# Volga-PCB.net
KiCad netlist of a schematic drawn in Altium Designer
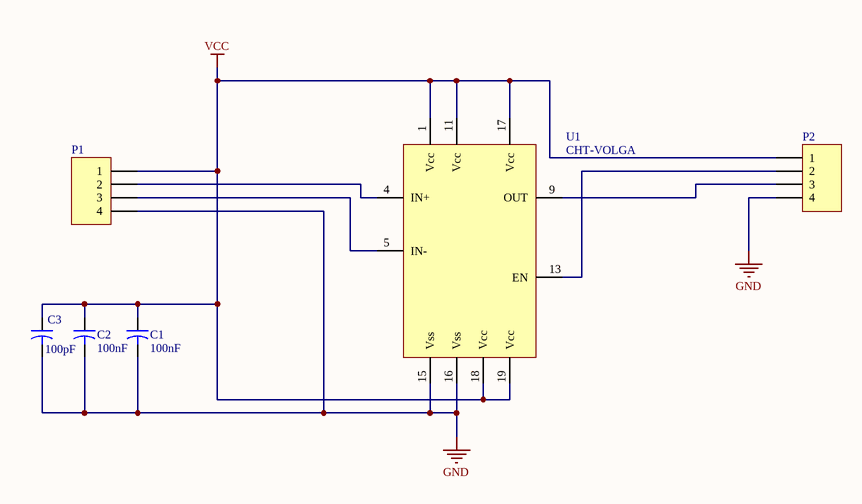
[diagram p0: Volga-PCB.SchDoc]

(export (version "E")
  (design (tool "Eeschema 10.0.6"))
  (components
    (comp (ref "C1")
      (value "100nF")
      (footprint "Dummy-10mm")
      (description "Capacitor-Dummy-THT")
      (fields (field (name "PUBLISHER") "Sebastian Kulik"))
      (libsource (lib "Capacitors") (part "Capacitor-Dummy-THT"))
    )
    (comp (ref "C2")
      (value "100nF")
      (footprint "Dummy-10mm")
      (description "Capacitor-Dummy-THT")
      (fields (field (name "PUBLISHER") "Sebastian Kulik"))
      (libsource (lib "Capacitors") (part "Capacitor-Dummy-THT"))
    )
    (comp (ref "C3")
      (value "100pF")
      (footprint "Dummy-10mm")
      (description "Capacitor-Dummy-THT")
      (fields (field (name "PUBLISHER") "Sebastian Kulik"))
      (libsource (lib "Capacitors") (part "Capacitor-Dummy-THT"))
    )
    (comp (ref "P1")
      (value "Plug_4_90_2.54")
      (footprint "HDR1X4")
      (description "Plug, 4-Pin")
      (fields (field (name "MANUFACTURER") "WE") (field (name "PUBLISHER") "Sebastian Kulik"))
      (libsource (lib "Connectors") (part "Plug_4_90_2.54"))
    )
    (comp (ref "P2")
      (value "Plug_4_90_2.54")
      (footprint "HDR1X4")
      (description "Plug, 4-Pin")
      (fields (field (name "MANUFACTURER") "WE") (field (name "PUBLISHER") "Sebastian Kulik"))
      (libsource (lib "") (part "Plug_4_90_2.54_1"))
    )
    (comp (ref "U1")
      (value "CHT-VOLGA")
      (footprint "TDFP16")
      (description "Comparator, Hi-Temp, 25MHz")
      (fields (field (name "MANUFACTURER") "CISSOID") (field (name "PUBLISHER") "Sebastian Kulik"))
      (libsource (lib "ICs") (part "CHT-VOLGA"))
    )
  )
  (nets
    (net (code "1") (name "GND") (class "Default")
      (node (ref "C1") (pin "2") (pinfunction "2_2") (pintype "passive"))
      (node (ref "C2") (pin "2") (pinfunction "2_2") (pintype "passive"))
      (node (ref "C3") (pin "2") (pinfunction "2_2") (pintype "passive"))
      (node (ref "P1") (pin "4") (pinfunction "4_4") (pintype "passive"))
      (node (ref "P2") (pin "4") (pinfunction "4_4") (pintype "passive"))
      (node (ref "U1") (pin "15") (pinfunction "Vss_15") (pintype "power_in"))
      (node (ref "U1") (pin "16") (pinfunction "Vss_16") (pintype "passive"))
    )
    (net (code "2") (name "Net-(U1-EN)") (class "Default")
      (node (ref "P2") (pin "2") (pinfunction "2_2") (pintype "passive"))
      (node (ref "U1") (pin "13") (pinfunction "EN_13") (pintype "passive"))
    )
    (net (code "3") (name "Net-(U1-IN+)") (class "Default")
      (node (ref "P1") (pin "2") (pinfunction "2_2") (pintype "passive"))
      (node (ref "U1") (pin "4") (pinfunction "IN+_4") (pintype "passive"))
    )
    (net (code "4") (name "Net-(U1-IN-)") (class "Default")
      (node (ref "P1") (pin "3") (pinfunction "3_3") (pintype "passive"))
      (node (ref "U1") (pin "5") (pinfunction "IN-_5") (pintype "passive"))
    )
    (net (code "5") (name "Net-(U1-OUT)") (class "Default")
      (node (ref "P2") (pin "3") (pinfunction "3_3") (pintype "passive"))
      (node (ref "U1") (pin "9") (pinfunction "OUT_9") (pintype "power_in"))
    )
    (net (code "6") (name "VCC") (class "Default")
      (node (ref "C1") (pin "1") (pinfunction "1_1") (pintype "passive"))
      (node (ref "C2") (pin "1") (pinfunction "1_1") (pintype "passive"))
      (node (ref "C3") (pin "1") (pinfunction "1_1") (pintype "passive"))
      (node (ref "P1") (pin "1") (pinfunction "1_1") (pintype "passive"))
      (node (ref "P2") (pin "1") (pinfunction "1_1") (pintype "passive"))
      (node (ref "U1") (pin "1") (pinfunction "Vcc_1") (pintype "passive"))
      (node (ref "U1") (pin "11") (pinfunction "Vcc_11") (pintype "power_in"))
      (node (ref "U1") (pin "17") (pinfunction "Vcc_17") (pintype "passive"))
      (node (ref "U1") (pin "18") (pinfunction "Vcc_18") (pintype "power_in"))
      (node (ref "U1") (pin "19") (pinfunction "Vcc_19") (pintype "power_in"))
    )
  )
)
